# Automatic_Night_Light.net
KiCad netlist of a schematic drawn in EasyEDA Pro
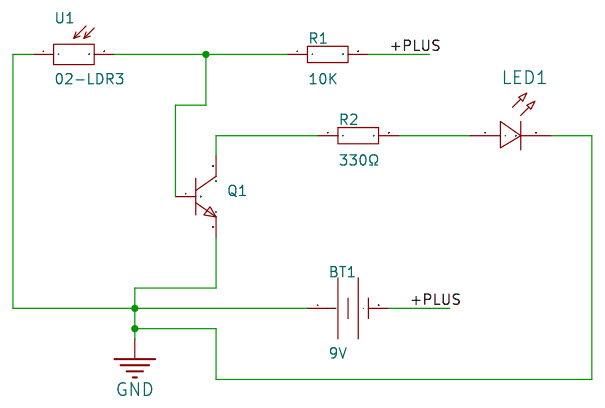
[diagram p0: schematic sheet]

(export (version "E")
  (design (tool "Eeschema 10.0.6"))
  (components
    (comp (ref "BT1")
      (value "9V")
      (footprint "easyedapro:BAT-TH_2P-9VBATTERY")
      (fields (field (name "Manufacturer") "Q&J"))
      (libsource (lib "easyedapro") (part "9V电池铜线扣 铜100MM"))
    )
    (comp (ref "LED1")
      (value "~")
      (footprint "easyedapro:LED0402-RD_YELLOW")
      (libsource (lib "easyedapro") (part "LED_R"))
    )
    (comp (ref "Q1")
      (value "~")
      (footprint "easyedapro:SOT-23_L2.9-W1.3-P1.90-LS2.4-BR")
      (libsource (lib "easyedapro") (part "NPN"))
    )
    (comp (ref "R1") (value "10K") (footprint "easyedapro:R0603") (libsource (lib "easyedapro") (part "Res")))
    (comp (ref "R2")
      (value "330Ω")
      (footprint "easyedapro:R0603")
      (libsource (lib "easyedapro") (part "Res"))
    )
    (comp (ref "U1")
      (value "02-LDR3")
      (footprint "easyedapro:RES-TH_L5.0-W4.3-P3.40-D0.5")
      (fields (field (name "Manufacturer") "NTE Electronics"))
      (libsource (lib "easyedapro") (part "02-LDR3"))
    )
  )
  (nets
    (net (code "1") (name "/+PLUS") (class "Default")
      (node (ref "BT1") (pin "2") (pinfunction "-_2") (pintype "unspecified"))
      (node (ref "R1") (pin "2") (pinfunction "2_2") (pintype "input"))
    )
    (net (code "2") (name "GND") (class "Default")
      (node (ref "BT1") (pin "1") (pinfunction "+_1") (pintype "unspecified"))
      (node (ref "LED1") (pin "2") (pinfunction "C_2") (pintype "input"))
      (node (ref "Q1") (pin "2") (pinfunction "E_2") (pintype "unspecified"))
      (node (ref "U1") (pin "1") (pinfunction "1_1") (pintype "unspecified"))
    )
    (net (code "3") (name "Net-(LED1-A)") (class "Default")
      (node (ref "LED1") (pin "1") (pinfunction "A_1") (pintype "input"))
      (node (ref "R2") (pin "2") (pinfunction "2_2") (pintype "input"))
    )
    (net (code "4") (name "Net-(Q1-B)") (class "Default")
      (node (ref "Q1") (pin "1") (pinfunction "B_1") (pintype "unspecified"))
      (node (ref "R1") (pin "1") (pinfunction "1_1") (pintype "input"))
      (node (ref "U1") (pin "2") (pinfunction "2_2") (pintype "unspecified"))
    )
    (net (code "5") (name "Net-(Q1-C)") (class "Default")
      (node (ref "Q1") (pin "3") (pinfunction "C_3") (pintype "unspecified"))
      (node (ref "R2") (pin "1") (pinfunction "1_1") (pintype "input"))
    )
  )
)
